# old_motor_line.net
KiCad netlist of a schematic drawn in EAGLE
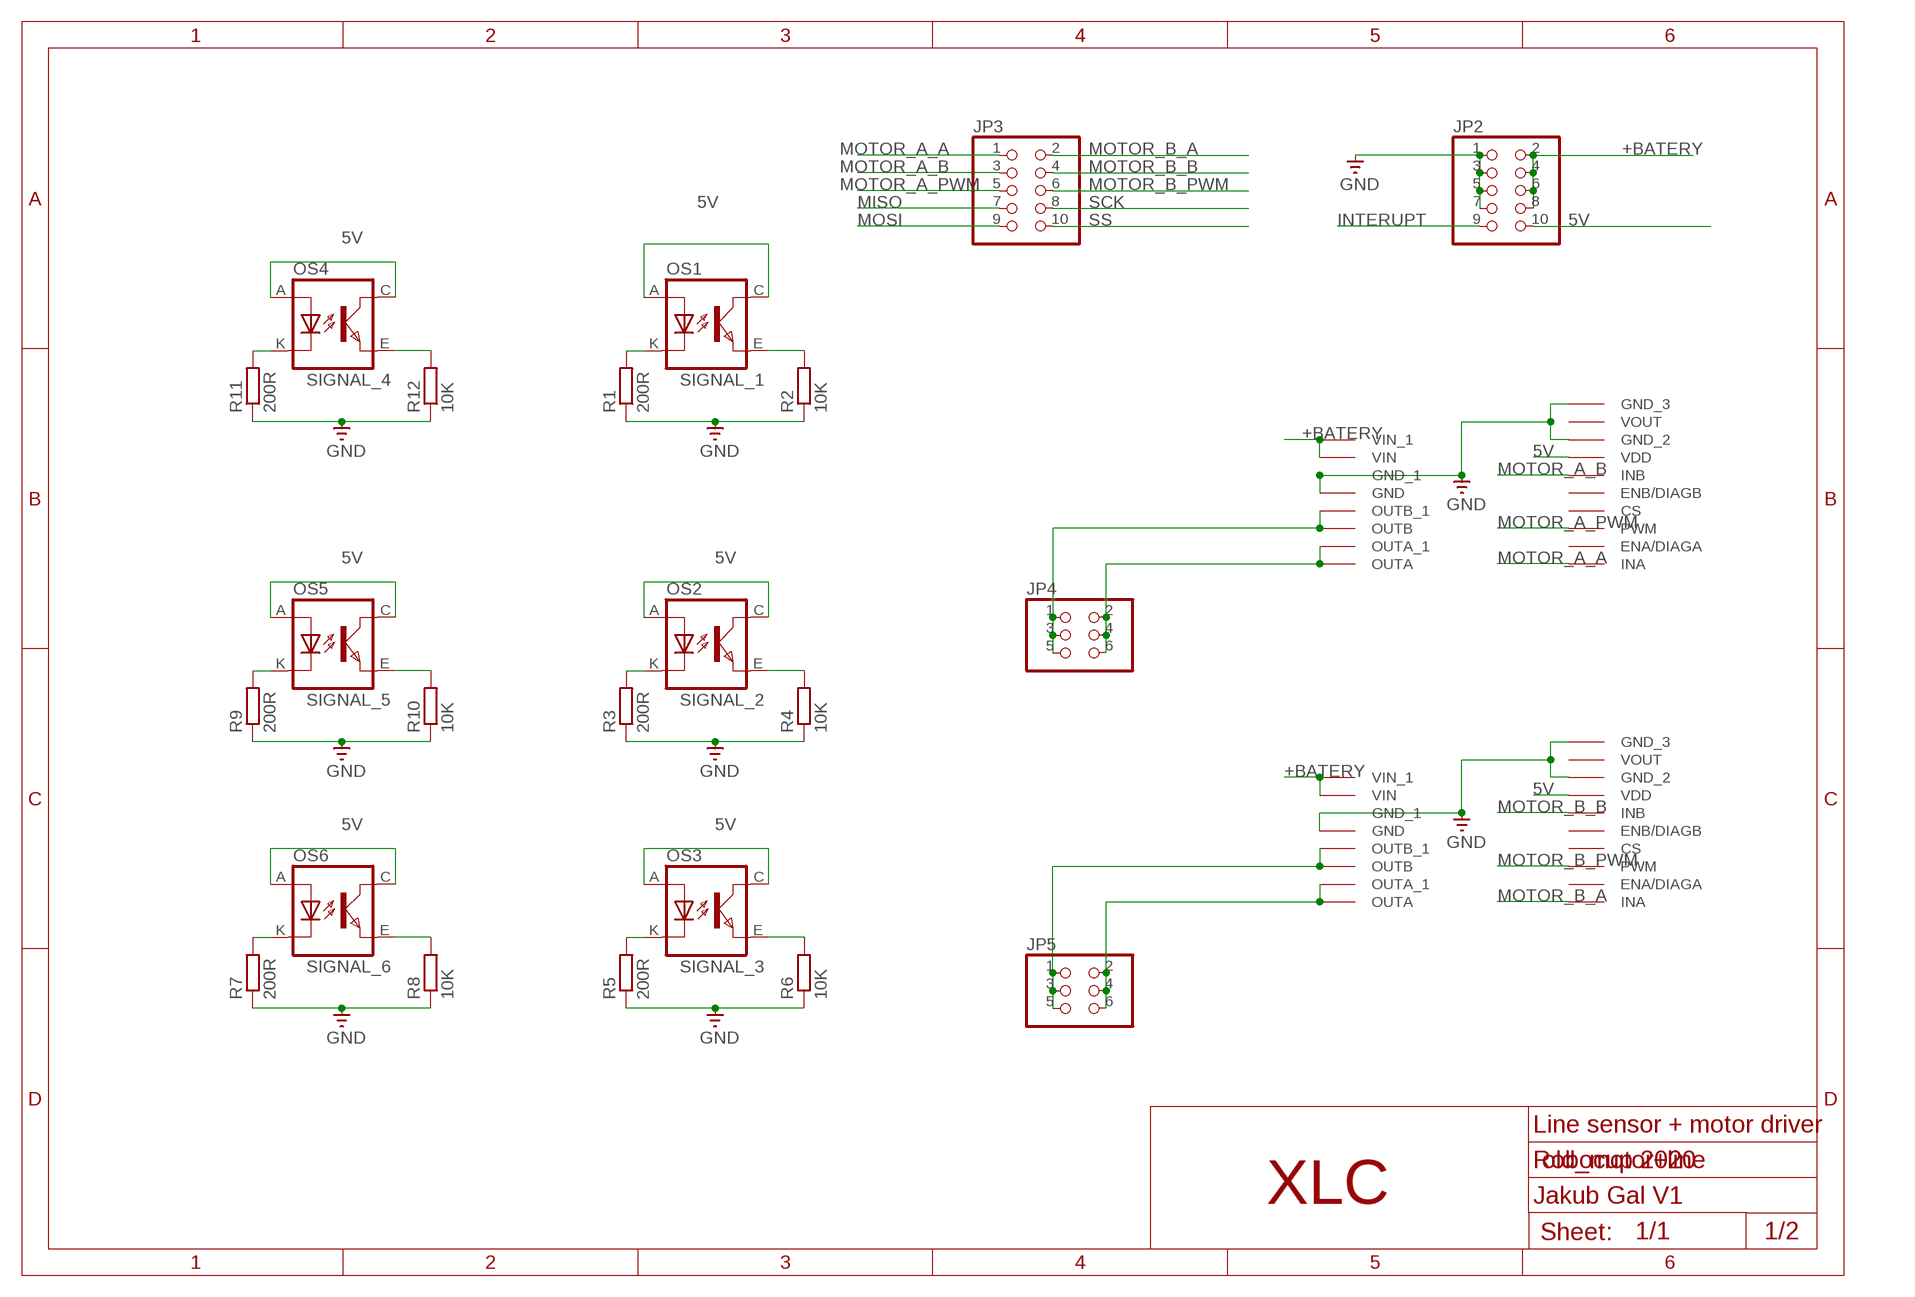
[diagram p0: schematic, sheet 1, part 1 of 2]
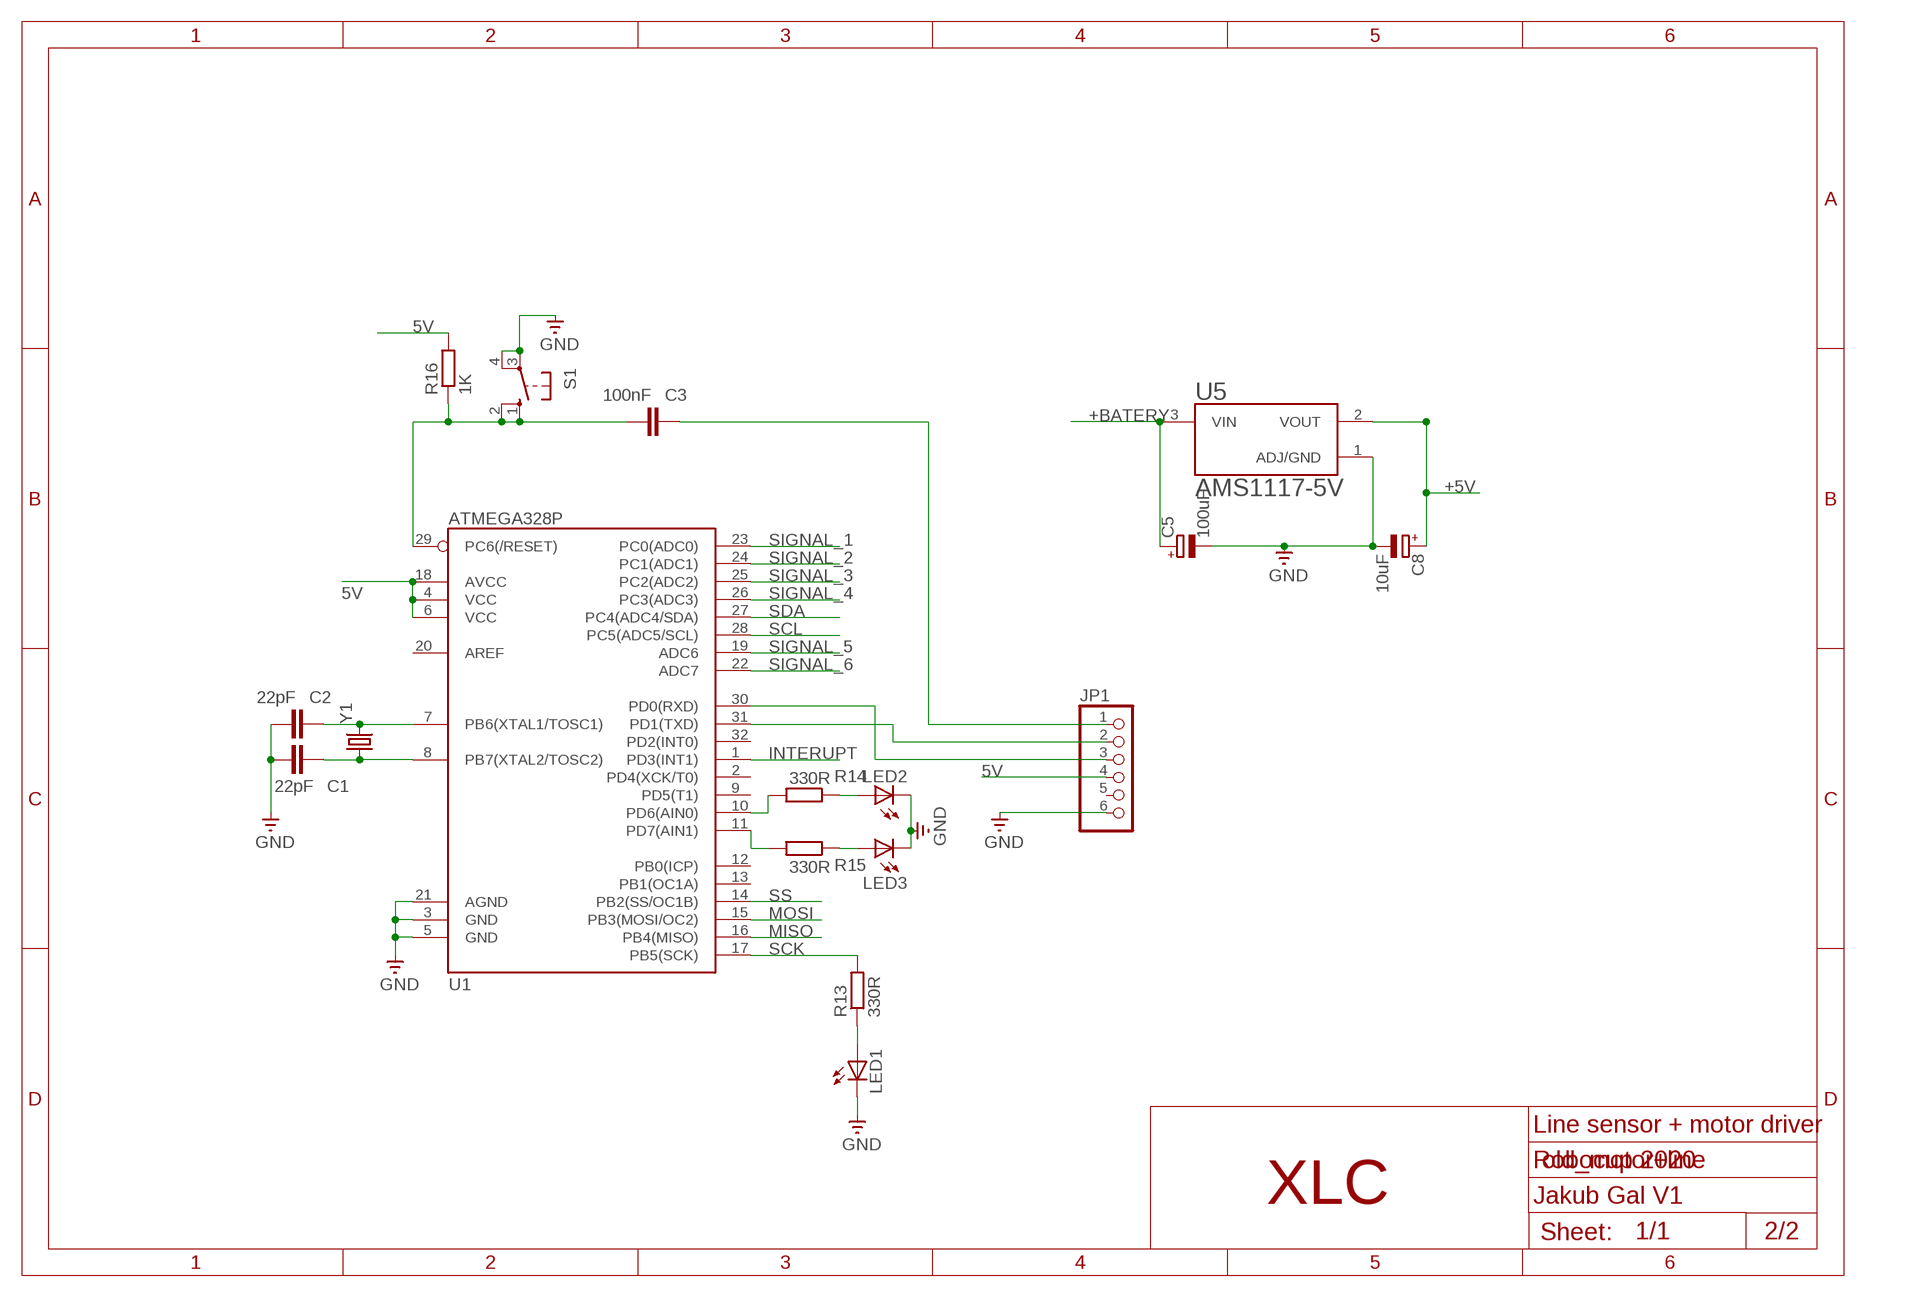
[diagram p1: schematic, sheet 1, part 2 of 2]

(export (version "E")
  (design (tool "Eeschema 10.0.6"))
  (components
    (comp (ref "C1")
      (value "22pF")
      (footprint "eagle-import:C0603")
      (libsource (lib "eagle-import") (part "C-EUC0603"))
    )
    (comp (ref "C2")
      (value "22pF")
      (footprint "eagle-import:C0603")
      (libsource (lib "eagle-import") (part "C-EUC0603"))
    )
    (comp (ref "C3")
      (value "100nF")
      (footprint "eagle-import:C0603")
      (libsource (lib "eagle-import") (part "C-EUC0603"))
    )
    (comp (ref "C5")
      (value "100uF")
      (footprint "eagle-import:UD-6,3X7,7_NICHICON")
      (libsource (lib "eagle-import") (part "CPOL-EUUD-6,3X7,7"))
    )
    (comp (ref "C8")
      (value "10uF")
      (footprint "eagle-import:UD-4X5,8_NICHICON")
      (libsource (lib "eagle-import") (part "CPOL-EUUD-4X5,8"))
    )
    (comp (ref "JP1")
      (value "PINHD-1X6/90")
      (footprint "eagle-import:1X06_90")
      (libsource (lib "eagle-import") (part "PINHD-1X6/90"))
    )
    (comp (ref "JP2")
      (value "PINHD-2X5")
      (footprint "eagle-import:2X05")
      (libsource (lib "eagle-import") (part "PINHD-2X5"))
    )
    (comp (ref "JP3")
      (value "PINHD-2X5")
      (footprint "eagle-import:2X05")
      (libsource (lib "eagle-import") (part "PINHD-2X5"))
    )
    (comp (ref "JP4")
      (value "PINHD-2X3")
      (footprint "eagle-import:2X03")
      (libsource (lib "eagle-import") (part "PINHD-2X3"))
    )
    (comp (ref "JP5")
      (value "PINHD-2X3")
      (footprint "eagle-import:2X03")
      (libsource (lib "eagle-import") (part "PINHD-2X3"))
    )
    (comp (ref "LED1")
      (value "LEDCHIPLED_0603")
      (footprint "eagle-import:CHIPLED_0603")
      (libsource (lib "eagle-import") (part "LEDCHIPLED_0603"))
    )
    (comp (ref "LED2")
      (value "LEDCHIPLED_0603")
      (footprint "eagle-import:CHIPLED_0603")
      (libsource (lib "eagle-import") (part "LEDCHIPLED_0603"))
    )
    (comp (ref "LED3")
      (value "LEDCHIPLED_0603")
      (footprint "eagle-import:CHIPLED_0603")
      (libsource (lib "eagle-import") (part "LEDCHIPLED_0603"))
    )
    (comp (ref "OS1")
      (value "TCRT5000")
      (footprint "eagle-import:TCRT5000")
      (libsource (lib "eagle-import") (part "TCRT5000"))
    )
    (comp (ref "OS2")
      (value "TCRT5000")
      (footprint "eagle-import:TCRT5000")
      (libsource (lib "eagle-import") (part "TCRT5000"))
    )
    (comp (ref "OS3")
      (value "TCRT5000")
      (footprint "eagle-import:TCRT5000")
      (libsource (lib "eagle-import") (part "TCRT5000"))
    )
    (comp (ref "OS4")
      (value "TCRT5000")
      (footprint "eagle-import:TCRT5000")
      (fields (field (name "SPICEPREFIX") "O"))
      (libsource (lib "eagle-import") (part "TCRT5000"))
    )
    (comp (ref "OS5")
      (value "TCRT5000")
      (footprint "eagle-import:TCRT5000")
      (libsource (lib "eagle-import") (part "TCRT5000"))
    )
    (comp (ref "OS6")
      (value "TCRT5000")
      (footprint "eagle-import:TCRT5000")
      (fields (field (name "SPICEPREFIX") "O"))
      (libsource (lib "eagle-import") (part "TCRT5000"))
    )
    (comp (ref "R1")
      (value "200R")
      (footprint "eagle-import:R0603")
      (libsource (lib "eagle-import") (part "R-EU_R0603"))
    )
    (comp (ref "R2")
      (value "10K")
      (footprint "eagle-import:R0603")
      (libsource (lib "eagle-import") (part "R-EU_R0603"))
    )
    (comp (ref "R3")
      (value "200R")
      (footprint "eagle-import:R0603")
      (libsource (lib "eagle-import") (part "R-EU_R0603"))
    )
    (comp (ref "R4")
      (value "10K")
      (footprint "eagle-import:R0603")
      (libsource (lib "eagle-import") (part "R-EU_R0603"))
    )
    (comp (ref "R5")
      (value "200R")
      (footprint "eagle-import:R0603")
      (libsource (lib "eagle-import") (part "R-EU_R0603"))
    )
    (comp (ref "R6")
      (value "10K")
      (footprint "eagle-import:R0603")
      (libsource (lib "eagle-import") (part "R-EU_R0603"))
    )
    (comp (ref "R7")
      (value "200R")
      (footprint "eagle-import:R0603")
      (libsource (lib "eagle-import") (part "R-EU_R0603"))
    )
    (comp (ref "R8")
      (value "10K")
      (footprint "eagle-import:R0603")
      (libsource (lib "eagle-import") (part "R-EU_R0603"))
    )
    (comp (ref "R9")
      (value "200R")
      (footprint "eagle-import:R0603")
      (libsource (lib "eagle-import") (part "R-EU_R0603"))
    )
    (comp (ref "R10")
      (value "10K")
      (footprint "eagle-import:R0603")
      (libsource (lib "eagle-import") (part "R-EU_R0603"))
    )
    (comp (ref "R11")
      (value "200R")
      (footprint "eagle-import:R0603")
      (libsource (lib "eagle-import") (part "R-EU_R0603"))
    )
    (comp (ref "R12")
      (value "10K")
      (footprint "eagle-import:R0603")
      (libsource (lib "eagle-import") (part "R-EU_R0603"))
    )
    (comp (ref "R13")
      (value "330R")
      (footprint "eagle-import:R0603")
      (libsource (lib "eagle-import") (part "R-EU_R0603"))
    )
    (comp (ref "R14")
      (value "330R")
      (footprint "eagle-import:R0603")
      (libsource (lib "eagle-import") (part "R-EU_R0603"))
    )
    (comp (ref "R15")
      (value "330R")
      (footprint "eagle-import:R0603")
      (libsource (lib "eagle-import") (part "R-EU_R0603"))
    )
    (comp (ref "R16")
      (value "1K")
      (footprint "eagle-import:R0603")
      (libsource (lib "eagle-import") (part "R-EU_R0603"))
    )
    (comp (ref "S1")
      (value "10-XX")
      (footprint "eagle-import:B3F-10XX")
      (fields (field (name "MPN") "B3F-1000"))
      (libsource (lib "eagle-import") (part "10-XX"))
    )
    (comp (ref "U$1")
      (value "MOTOR_DRIVER")
      (footprint "eagle-import:MOTOR_DRIVER")
      (libsource (lib "eagle-import") (part "MOTOR_DRIVER"))
    )
    (comp (ref "U$2")
      (value "MOTOR_DRIVER")
      (footprint "eagle-import:MOTOR_DRIVER")
      (libsource (lib "eagle-import") (part "MOTOR_DRIVER"))
    )
    (comp (ref "U1")
      (value "ATMEGA328P")
      (footprint "eagle-import:TQFP32-08")
      (libsource (lib "eagle-import") (part "ATMEGA328_SMT"))
    )
    (comp (ref "U5")
      (value "AMS1117-5V")
      (footprint "eagle-import:SOT229P700X180-4N")
      (fields (field (name "MF") "Advanced Monolithic Systems") (field (name "MP") "AMS1117-3.3"))
      (libsource (lib "eagle-import") (part "AMS1117-3.3"))
    )
    (comp (ref "Y1")
      (value "CRYSTALHC49US")
      (footprint "eagle-import:HC49US")
      (libsource (lib "eagle-import") (part "CRYSTALHC49US"))
    )
  )
  (nets
    (net (code "1") (name "/+5V") (class "Default")
      (node (ref "C8") (pin "+") (pinfunction "+_+") (pintype "passive"))
      (node (ref "U5") (pin "2") (pinfunction "VOUT_2") (pintype "output"))
    )
    (net (code "2") (name "/+BATERY") (class "Default")
      (node (ref "C5") (pin "+") (pinfunction "+_+") (pintype "passive"))
      (node (ref "JP2") (pin "2") (pinfunction "2_2") (pintype "passive"))
      (node (ref "JP2") (pin "4") (pinfunction "4_4") (pintype "passive"))
      (node (ref "JP2") (pin "6") (pinfunction "6_6") (pintype "passive"))
      (node (ref "JP2") (pin "8") (pinfunction "8_8") (pintype "passive"))
      (node (ref "U$1") (pin "VIN") (pinfunction "VIN_VIN") (pintype "bidirectional"))
      (node (ref "U$1") (pin "VIN_1") (pinfunction "VIN_1_VIN_1") (pintype "bidirectional"))
      (node (ref "U$2") (pin "VIN") (pinfunction "VIN_VIN") (pintype "bidirectional"))
      (node (ref "U$2") (pin "VIN_1") (pinfunction "VIN_1_VIN_1") (pintype "bidirectional"))
      (node (ref "U5") (pin "3") (pinfunction "VIN_3") (pintype "input"))
    )
    (net (code "3") (name "/5V") (class "Default")
      (node (ref "JP1") (pin "4") (pinfunction "4_4") (pintype "passive"))
      (node (ref "JP2") (pin "10") (pinfunction "10_10") (pintype "passive"))
      (node (ref "OS1") (pin "A") (pinfunction "ANODE_A") (pintype "passive"))
      (node (ref "OS1") (pin "C") (pinfunction "COLLECTOR_C") (pintype "passive"))
      (node (ref "OS2") (pin "A") (pinfunction "ANODE_A") (pintype "passive"))
      (node (ref "OS2") (pin "C") (pinfunction "COLLECTOR_C") (pintype "passive"))
      (node (ref "OS3") (pin "A") (pinfunction "ANODE_A") (pintype "passive"))
      (node (ref "OS3") (pin "C") (pinfunction "COLLECTOR_C") (pintype "passive"))
      (node (ref "OS4") (pin "A") (pinfunction "ANODE_A") (pintype "passive"))
      (node (ref "OS4") (pin "C") (pinfunction "COLLECTOR_C") (pintype "passive"))
      (node (ref "OS5") (pin "A") (pinfunction "ANODE_A") (pintype "passive"))
      (node (ref "OS5") (pin "C") (pinfunction "COLLECTOR_C") (pintype "passive"))
      (node (ref "OS6") (pin "A") (pinfunction "ANODE_A") (pintype "passive"))
      (node (ref "OS6") (pin "C") (pinfunction "COLLECTOR_C") (pintype "passive"))
      (node (ref "R16") (pin "2") (pinfunction "2_2") (pintype "passive"))
      (node (ref "U$1") (pin "VDD") (pinfunction "VDD_VDD") (pintype "bidirectional"))
      (node (ref "U$2") (pin "VDD") (pinfunction "VDD_VDD") (pintype "bidirectional"))
      (node (ref "U1") (pin "18") (pinfunction "AVCC_18") (pintype "bidirectional"))
      (node (ref "U1") (pin "4") (pinfunction "VCC_4") (pintype "bidirectional"))
      (node (ref "U1") (pin "6") (pinfunction "VCC_6") (pintype "bidirectional"))
    )
    (net (code "4") (name "/INTERUPT") (class "Default")
      (node (ref "JP2") (pin "9") (pinfunction "9_9") (pintype "passive"))
      (node (ref "U1") (pin "1") (pinfunction "PD3(INT1)_1") (pintype "bidirectional"))
    )
    (net (code "5") (name "/MISO") (class "Default")
      (node (ref "JP3") (pin "7") (pinfunction "7_7") (pintype "passive"))
      (node (ref "U1") (pin "16") (pinfunction "PB4(MISO)_16") (pintype "bidirectional"))
    )
    (net (code "6") (name "/MOSI") (class "Default")
      (node (ref "JP3") (pin "9") (pinfunction "9_9") (pintype "passive"))
      (node (ref "U1") (pin "15") (pinfunction "PB3(MOSI/OC2)_15") (pintype "bidirectional"))
    )
    (net (code "7") (name "/MOTOR_A_A") (class "Default")
      (node (ref "JP3") (pin "1") (pinfunction "1_1") (pintype "passive"))
      (node (ref "U$1") (pin "INA") (pinfunction "INA_INA") (pintype "bidirectional"))
    )
    (net (code "8") (name "/MOTOR_A_B") (class "Default")
      (node (ref "JP3") (pin "3") (pinfunction "3_3") (pintype "passive"))
      (node (ref "U$1") (pin "INB") (pinfunction "INB_INB") (pintype "bidirectional"))
    )
    (net (code "9") (name "/MOTOR_A_PWM") (class "Default")
      (node (ref "JP3") (pin "5") (pinfunction "5_5") (pintype "passive"))
      (node (ref "U$1") (pin "PWM") (pinfunction "PWM_PWM") (pintype "bidirectional"))
    )
    (net (code "10") (name "/MOTOR_B_A") (class "Default")
      (node (ref "JP3") (pin "2") (pinfunction "2_2") (pintype "passive"))
      (node (ref "U$2") (pin "INA") (pinfunction "INA_INA") (pintype "bidirectional"))
    )
    (net (code "11") (name "/MOTOR_B_B") (class "Default")
      (node (ref "JP3") (pin "4") (pinfunction "4_4") (pintype "passive"))
      (node (ref "U$2") (pin "INB") (pinfunction "INB_INB") (pintype "bidirectional"))
    )
    (net (code "12") (name "/MOTOR_B_PWM") (class "Default")
      (node (ref "JP3") (pin "6") (pinfunction "6_6") (pintype "passive"))
      (node (ref "U$2") (pin "PWM") (pinfunction "PWM_PWM") (pintype "bidirectional"))
    )
    (net (code "13") (name "/SCK") (class "Default")
      (node (ref "JP3") (pin "8") (pinfunction "8_8") (pintype "passive"))
      (node (ref "R13") (pin "2") (pinfunction "2_2") (pintype "passive"))
      (node (ref "U1") (pin "17") (pinfunction "PB5(SCK)_17") (pintype "bidirectional"))
    )
    (net (code "14") (name "/SCL") (class "Default")
      (node (ref "U1") (pin "28") (pinfunction "PC5(ADC5/SCL)_28") (pintype "bidirectional"))
    )
    (net (code "15") (name "/SDA") (class "Default")
      (node (ref "U1") (pin "27") (pinfunction "PC4(ADC4/SDA)_27") (pintype "bidirectional"))
    )
    (net (code "16") (name "/SIGNAL_1") (class "Default")
      (node (ref "OS1") (pin "E") (pinfunction "EMITTER_E") (pintype "passive"))
      (node (ref "R2") (pin "2") (pinfunction "2_2") (pintype "passive"))
      (node (ref "U1") (pin "23") (pinfunction "PC0(ADC0)_23") (pintype "bidirectional"))
    )
    (net (code "17") (name "/SIGNAL_2") (class "Default")
      (node (ref "OS2") (pin "E") (pinfunction "EMITTER_E") (pintype "passive"))
      (node (ref "R4") (pin "2") (pinfunction "2_2") (pintype "passive"))
      (node (ref "U1") (pin "24") (pinfunction "PC1(ADC1)_24") (pintype "bidirectional"))
    )
    (net (code "18") (name "/SIGNAL_3") (class "Default")
      (node (ref "OS3") (pin "E") (pinfunction "EMITTER_E") (pintype "passive"))
      (node (ref "R6") (pin "2") (pinfunction "2_2") (pintype "passive"))
      (node (ref "U1") (pin "25") (pinfunction "PC2(ADC2)_25") (pintype "bidirectional"))
    )
    (net (code "19") (name "/SIGNAL_4") (class "Default")
      (node (ref "OS4") (pin "E") (pinfunction "EMITTER_E") (pintype "passive"))
      (node (ref "R12") (pin "2") (pinfunction "2_2") (pintype "passive"))
      (node (ref "U1") (pin "26") (pinfunction "PC3(ADC3)_26") (pintype "bidirectional"))
    )
    (net (code "20") (name "/SIGNAL_5") (class "Default")
      (node (ref "OS5") (pin "E") (pinfunction "EMITTER_E") (pintype "passive"))
      (node (ref "R10") (pin "2") (pinfunction "2_2") (pintype "passive"))
      (node (ref "U1") (pin "19") (pinfunction "ADC6_19") (pintype "bidirectional"))
    )
    (net (code "21") (name "/SIGNAL_6") (class "Default")
      (node (ref "OS6") (pin "E") (pinfunction "EMITTER_E") (pintype "passive"))
      (node (ref "R8") (pin "2") (pinfunction "2_2") (pintype "passive"))
      (node (ref "U1") (pin "22") (pinfunction "ADC7_22") (pintype "bidirectional"))
    )
    (net (code "22") (name "/SS") (class "Default")
      (node (ref "JP3") (pin "10") (pinfunction "10_10") (pintype "passive"))
      (node (ref "U1") (pin "14") (pinfunction "PB2(SS/OC1B)_14") (pintype "bidirectional"))
    )
    (net (code "23") (name "GND") (class "Default")
      (node (ref "C1") (pin "1") (pinfunction "1_1") (pintype "passive"))
      (node (ref "C2") (pin "1") (pinfunction "1_1") (pintype "passive"))
      (node (ref "C5") (pin "-") (pinfunction "-_-") (pintype "passive"))
      (node (ref "C8") (pin "-") (pinfunction "-_-") (pintype "passive"))
      (node (ref "JP1") (pin "6") (pinfunction "6_6") (pintype "passive"))
      (node (ref "JP2") (pin "1") (pinfunction "1_1") (pintype "passive"))
      (node (ref "JP2") (pin "3") (pinfunction "3_3") (pintype "passive"))
      (node (ref "JP2") (pin "5") (pinfunction "5_5") (pintype "passive"))
      (node (ref "JP2") (pin "7") (pinfunction "7_7") (pintype "passive"))
      (node (ref "LED1") (pin "C") (pinfunction "C_C") (pintype "passive"))
      (node (ref "LED2") (pin "C") (pinfunction "C_C") (pintype "passive"))
      (node (ref "LED3") (pin "C") (pinfunction "C_C") (pintype "passive"))
      (node (ref "R1") (pin "1") (pinfunction "1_1") (pintype "passive"))
      (node (ref "R10") (pin "1") (pinfunction "1_1") (pintype "passive"))
      (node (ref "R11") (pin "1") (pinfunction "1_1") (pintype "passive"))
      (node (ref "R12") (pin "1") (pinfunction "1_1") (pintype "passive"))
      (node (ref "R2") (pin "1") (pinfunction "1_1") (pintype "passive"))
      (node (ref "R3") (pin "1") (pinfunction "1_1") (pintype "passive"))
      (node (ref "R4") (pin "1") (pinfunction "1_1") (pintype "passive"))
      (node (ref "R5") (pin "1") (pinfunction "1_1") (pintype "passive"))
      (node (ref "R6") (pin "1") (pinfunction "1_1") (pintype "passive"))
      (node (ref "R7") (pin "1") (pinfunction "1_1") (pintype "passive"))
      (node (ref "R8") (pin "1") (pinfunction "1_1") (pintype "passive"))
      (node (ref "R9") (pin "1") (pinfunction "1_1") (pintype "passive"))
      (node (ref "S1") (pin "3") (pinfunction "P_3") (pintype "passive"))
      (node (ref "S1") (pin "4") (pinfunction "P1_4") (pintype "passive"))
      (node (ref "U$1") (pin "GND") (pinfunction "GND_GND") (pintype "bidirectional"))
      (node (ref "U$1") (pin "GND_1") (pinfunction "GND_1_GND_1") (pintype "bidirectional"))
      (node (ref "U$1") (pin "GND_2") (pinfunction "GND_2_GND_2") (pintype "bidirectional"))
      (node (ref "U$1") (pin "GND_3") (pinfunction "GND_3_GND_3") (pintype "bidirectional"))
      (node (ref "U$2") (pin "GND") (pinfunction "GND_GND") (pintype "bidirectional"))
      (node (ref "U$2") (pin "GND_1") (pinfunction "GND_1_GND_1") (pintype "bidirectional"))
      (node (ref "U$2") (pin "GND_2") (pinfunction "GND_2_GND_2") (pintype "bidirectional"))
      (node (ref "U$2") (pin "GND_3") (pinfunction "GND_3_GND_3") (pintype "bidirectional"))
      (node (ref "U1") (pin "21") (pinfunction "AGND_21") (pintype "bidirectional"))
      (node (ref "U1") (pin "3") (pinfunction "GND_3") (pintype "bidirectional"))
      (node (ref "U1") (pin "5") (pinfunction "GND_5") (pintype "bidirectional"))
      (node (ref "U5") (pin "1") (pinfunction "ADJ/GND_1") (pintype "power_in"))
    )
    (net (code "24") (name "Net-(C3-Pad2)") (class "Default")
      (node (ref "C3") (pin "2") (pinfunction "2_2") (pintype "passive"))
      (node (ref "JP1") (pin "1") (pinfunction "1_1") (pintype "passive"))
    )
    (net (code "25") (name "Net-(JP4-Pad1)") (class "Default")
      (node (ref "JP4") (pin "1") (pinfunction "1_1") (pintype "passive"))
      (node (ref "JP4") (pin "3") (pinfunction "3_3") (pintype "passive"))
      (node (ref "JP4") (pin "5") (pinfunction "5_5") (pintype "passive"))
      (node (ref "U$1") (pin "OUTB") (pinfunction "OUTB_OUTB") (pintype "bidirectional"))
      (node (ref "U$1") (pin "OUTB_1") (pinfunction "OUTB_1_OUTB_1") (pintype "bidirectional"))
    )
    (net (code "26") (name "Net-(JP4-Pad2)") (class "Default")
      (node (ref "JP4") (pin "2") (pinfunction "2_2") (pintype "passive"))
      (node (ref "JP4") (pin "4") (pinfunction "4_4") (pintype "passive"))
      (node (ref "JP4") (pin "6") (pinfunction "6_6") (pintype "passive"))
      (node (ref "U$1") (pin "OUTA") (pinfunction "OUTA_OUTA") (pintype "bidirectional"))
      (node (ref "U$1") (pin "OUTA_1") (pinfunction "OUTA_1_OUTA_1") (pintype "bidirectional"))
    )
    (net (code "27") (name "Net-(JP5-Pad1)") (class "Default")
      (node (ref "JP5") (pin "1") (pinfunction "1_1") (pintype "passive"))
      (node (ref "JP5") (pin "3") (pinfunction "3_3") (pintype "passive"))
      (node (ref "JP5") (pin "5") (pinfunction "5_5") (pintype "passive"))
      (node (ref "U$2") (pin "OUTB") (pinfunction "OUTB_OUTB") (pintype "bidirectional"))
      (node (ref "U$2") (pin "OUTB_1") (pinfunction "OUTB_1_OUTB_1") (pintype "bidirectional"))
    )
    (net (code "28") (name "Net-(JP5-Pad2)") (class "Default")
      (node (ref "JP5") (pin "2") (pinfunction "2_2") (pintype "passive"))
      (node (ref "JP5") (pin "4") (pinfunction "4_4") (pintype "passive"))
      (node (ref "JP5") (pin "6") (pinfunction "6_6") (pintype "passive"))
      (node (ref "U$2") (pin "OUTA") (pinfunction "OUTA_OUTA") (pintype "bidirectional"))
      (node (ref "U$2") (pin "OUTA_1") (pinfunction "OUTA_1_OUTA_1") (pintype "bidirectional"))
    )
    (net (code "29") (name "Net-(LED1-PadA)") (class "Default")
      (node (ref "LED1") (pin "A") (pinfunction "A_A") (pintype "passive"))
      (node (ref "R13") (pin "1") (pinfunction "1_1") (pintype "passive"))
    )
    (net (code "30") (name "Net-(LED2-PadA)") (class "Default")
      (node (ref "LED2") (pin "A") (pinfunction "A_A") (pintype "passive"))
      (node (ref "R14") (pin "1") (pinfunction "1_1") (pintype "passive"))
    )
    (net (code "31") (name "Net-(LED3-PadA)") (class "Default")
      (node (ref "LED3") (pin "A") (pinfunction "A_A") (pintype "passive"))
      (node (ref "R15") (pin "1") (pinfunction "1_1") (pintype "passive"))
    )
    (net (code "32") (name "Net-(OS1-CATHODE)") (class "Default")
      (node (ref "OS1") (pin "K") (pinfunction "CATHODE_K") (pintype "passive"))
      (node (ref "R1") (pin "2") (pinfunction "2_2") (pintype "passive"))
    )
    (net (code "33") (name "Net-(OS2-CATHODE)") (class "Default")
      (node (ref "OS2") (pin "K") (pinfunction "CATHODE_K") (pintype "passive"))
      (node (ref "R3") (pin "2") (pinfunction "2_2") (pintype "passive"))
    )
    (net (code "34") (name "Net-(OS3-CATHODE)") (class "Default")
      (node (ref "OS3") (pin "K") (pinfunction "CATHODE_K") (pintype "passive"))
      (node (ref "R5") (pin "2") (pinfunction "2_2") (pintype "passive"))
    )
    (net (code "35") (name "Net-(OS4-CATHODE)") (class "Default")
      (node (ref "OS4") (pin "K") (pinfunction "CATHODE_K") (pintype "passive"))
      (node (ref "R11") (pin "2") (pinfunction "2_2") (pintype "passive"))
    )
    (net (code "36") (name "Net-(OS5-CATHODE)") (class "Default")
      (node (ref "OS5") (pin "K") (pinfunction "CATHODE_K") (pintype "passive"))
      (node (ref "R9") (pin "2") (pinfunction "2_2") (pintype "passive"))
    )
    (net (code "37") (name "Net-(OS6-CATHODE)") (class "Default")
      (node (ref "OS6") (pin "K") (pinfunction "CATHODE_K") (pintype "passive"))
      (node (ref "R7") (pin "2") (pinfunction "2_2") (pintype "passive"))
    )
    (net (code "38") (name "Net-(S1-S)") (class "Default")
      (node (ref "C3") (pin "1") (pinfunction "1_1") (pintype "passive"))
      (node (ref "R16") (pin "1") (pinfunction "1_1") (pintype "passive"))
      (node (ref "S1") (pin "1") (pinfunction "S_1") (pintype "passive"))
      (node (ref "S1") (pin "2") (pinfunction "S1_2") (pintype "passive"))
      (node (ref "U1") (pin "29") (pinfunction "PC6(/RESET)_29") (pintype "bidirectional"))
    )
    (net (code "39") (name "Net-(U1-PB6(XTAL1{slash}TOSC1))") (class "Default")
      (node (ref "C2") (pin "2") (pinfunction "2_2") (pintype "passive"))
      (node (ref "U1") (pin "7") (pinfunction "PB6(XTAL1/TOSC1)_7") (pintype "bidirectional"))
      (node (ref "Y1") (pin "2") (pinfunction "2_2") (pintype "passive"))
    )
    (net (code "40") (name "Net-(U1-PB7(XTAL2{slash}TOSC2))") (class "Default")
      (node (ref "C1") (pin "2") (pinfunction "2_2") (pintype "passive"))
      (node (ref "U1") (pin "8") (pinfunction "PB7(XTAL2/TOSC2)_8") (pintype "bidirectional"))
      (node (ref "Y1") (pin "1") (pinfunction "1_1") (pintype "passive"))
    )
    (net (code "41") (name "Net-(U1-PD0(RXD))") (class "Default")
      (node (ref "JP1") (pin "3") (pinfunction "3_3") (pintype "passive"))
      (node (ref "U1") (pin "30") (pinfunction "PD0(RXD)_30") (pintype "bidirectional"))
    )
    (net (code "42") (name "Net-(U1-PD1(TXD))") (class "Default")
      (node (ref "JP1") (pin "2") (pinfunction "2_2") (pintype "passive"))
      (node (ref "U1") (pin "31") (pinfunction "PD1(TXD)_31") (pintype "bidirectional"))
    )
    (net (code "43") (name "Net-(U1-PD6(AIN0))") (class "Default")
      (node (ref "R14") (pin "2") (pinfunction "2_2") (pintype "passive"))
      (node (ref "U1") (pin "10") (pinfunction "PD6(AIN0)_10") (pintype "bidirectional"))
    )
    (net (code "44") (name "Net-(U1-PD7(AIN1))") (class "Default")
      (node (ref "R15") (pin "2") (pinfunction "2_2") (pintype "passive"))
      (node (ref "U1") (pin "11") (pinfunction "PD7(AIN1)_11") (pintype "bidirectional"))
    )
    (net (code "45") (name "unconnected-(JP1-Pad5)") (class "Default")
      (node (ref "JP1") (pin "5") (pinfunction "5_5") (pintype "passive"))
    )
    (net (code "46") (name "unconnected-(U$1-PadCS)") (class "Default")
      (node (ref "U$1") (pin "CS") (pinfunction "CS_CS") (pintype "bidirectional"))
    )
    (net (code "47") (name "unconnected-(U$1-PadENA{slash}DIAGA)") (class "Default")
      (node (ref "U$1") (pin "ENA/DIAGA") (pinfunction "ENA/DIAGA_ENA/DIAGA") (pintype "bidirectional"))
    )
    (net (code "48") (name "unconnected-(U$1-PadENB{slash}DIAGB)") (class "Default")
      (node (ref "U$1") (pin "ENB/DIAGB") (pinfunction "ENB/DIAGB_ENB/DIAGB") (pintype "bidirectional"))
    )
    (net (code "49") (name "unconnected-(U$1-PadVOUT)") (class "Default")
      (node (ref "U$1") (pin "VOUT") (pinfunction "VOUT_VOUT") (pintype "bidirectional"))
    )
    (net (code "50") (name "unconnected-(U$2-PadCS)") (class "Default")
      (node (ref "U$2") (pin "CS") (pinfunction "CS_CS") (pintype "bidirectional"))
    )
    (net (code "51") (name "unconnected-(U$2-PadENA{slash}DIAGA)") (class "Default")
      (node (ref "U$2") (pin "ENA/DIAGA") (pinfunction "ENA/DIAGA_ENA/DIAGA") (pintype "bidirectional"))
    )
    (net (code "52") (name "unconnected-(U$2-PadENB{slash}DIAGB)") (class "Default")
      (node (ref "U$2") (pin "ENB/DIAGB") (pinfunction "ENB/DIAGB_ENB/DIAGB") (pintype "bidirectional"))
    )
    (net (code "53") (name "unconnected-(U$2-PadVOUT)") (class "Default")
      (node (ref "U$2") (pin "VOUT") (pinfunction "VOUT_VOUT") (pintype "bidirectional"))
    )
    (net (code "54") (name "unconnected-(U1-AREF-Pad20)") (class "Default")
      (node (ref "U1") (pin "20") (pinfunction "AREF_20") (pintype "bidirectional"))
    )
    (net (code "55") (name "unconnected-(U1-PB0(ICP)-Pad12)") (class "Default")
      (node (ref "U1") (pin "12") (pinfunction "PB0(ICP)_12") (pintype "bidirectional"))
    )
    (net (code "56") (name "unconnected-(U1-PB1(OC1A)-Pad13)") (class "Default")
      (node (ref "U1") (pin "13") (pinfunction "PB1(OC1A)_13") (pintype "bidirectional"))
    )
    (net (code "57") (name "unconnected-(U1-PD2(INT0)-Pad32)") (class "Default")
      (node (ref "U1") (pin "32") (pinfunction "PD2(INT0)_32") (pintype "bidirectional"))
    )
    (net (code "58") (name "unconnected-(U1-PD4(XCK{slash}T0)-Pad2)") (class "Default")
      (node (ref "U1") (pin "2") (pinfunction "PD4(XCK/T0)_2") (pintype "bidirectional"))
    )
    (net (code "59") (name "unconnected-(U1-PD5(T1)-Pad9)") (class "Default")
      (node (ref "U1") (pin "9") (pinfunction "PD5(T1)_9") (pintype "bidirectional"))
    )
  )
)
